# EPS_Connectors.net
KiCad netlist of a schematic drawn in Altium Designer
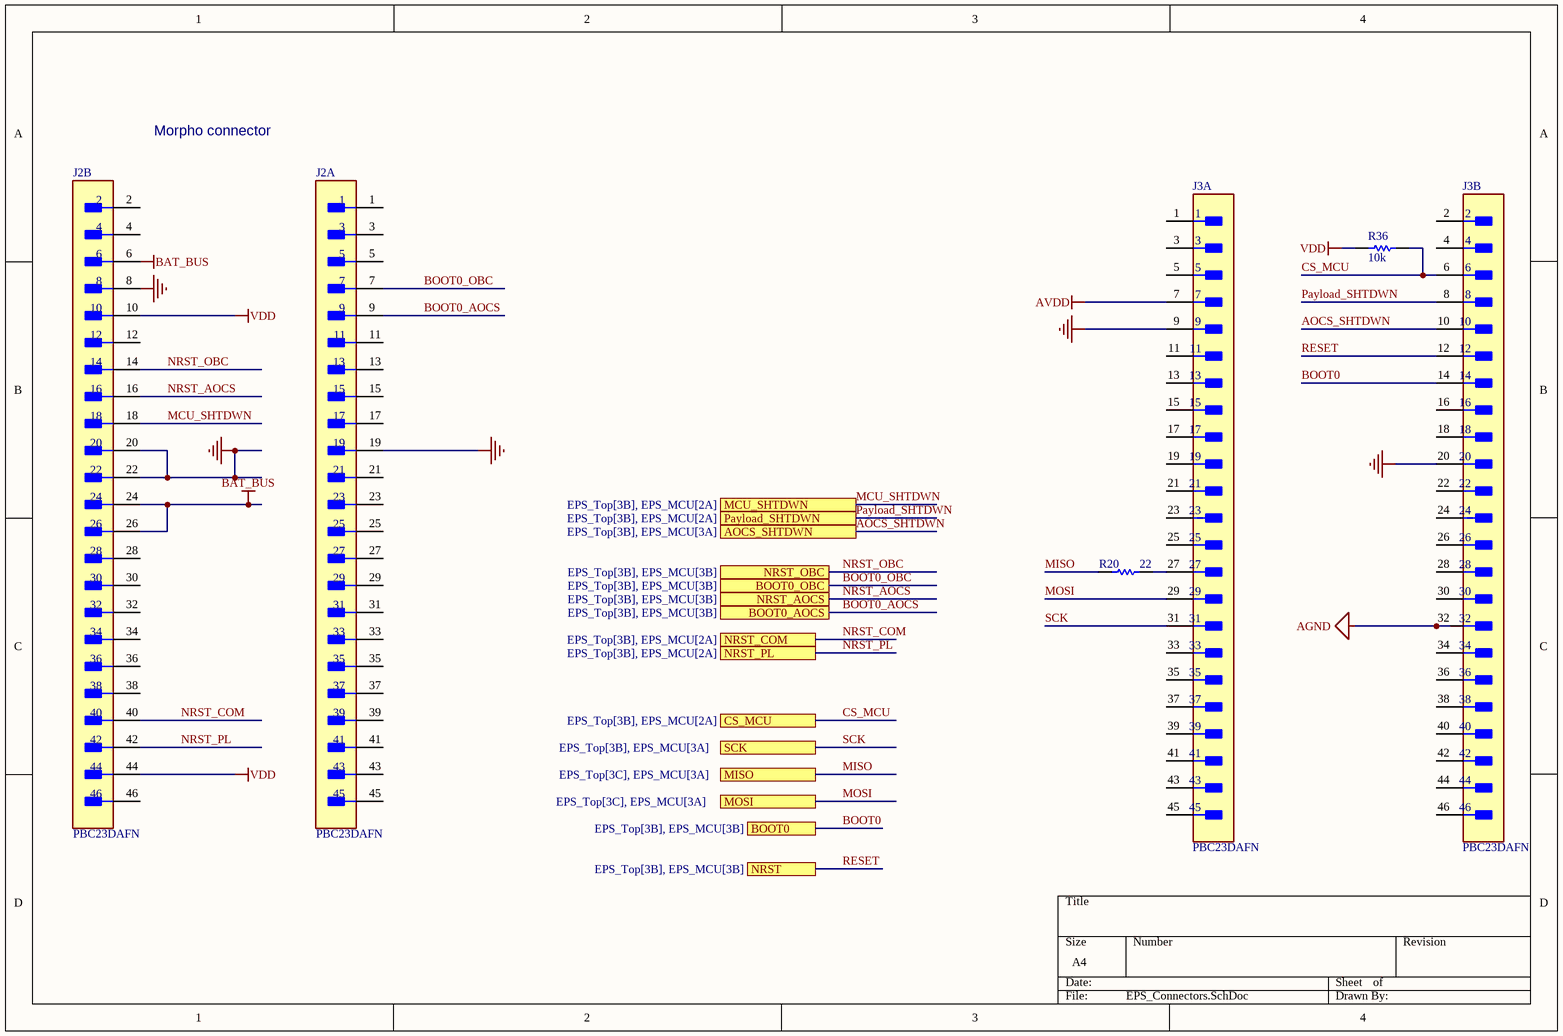
[diagram p0: EPS_Connectors.SchDoc]

(export (version "E")
  (design (tool "Eeschema 10.0.6"))
  (components
    (comp (ref "J2")
      (value "PBC23DAFN")
      (footprint "FP-PBC23DAFN-MFG")
      (description "CONN HEADER VERT 46POS 2.54MM")
      (libsource (lib "Altium Content Vault") (part "9d336348a4f8d78a7f3b81cc8d27765"))
    )
    (comp (ref "J3")
      (value "PBC23DAFN")
      (footprint "FP-PBC23DAFN-MFG")
      (description "CONN HEADER VERT 46POS 2.54MM")
      (libsource (lib "Altium Content Vault") (part "9d336348a4f8d78a7f3b81cc8d27765"))
    )
    (comp (ref "R20")
      (value "22")
      (footprint "RESC1608X55X25NL10T15")
      (description "Chip Resistor, 22 Ohm, +/- 1%, 0.1 W, -55 to 155 degC, 0603 (1608 Metric), RoHS, Tape and Reel")
      (libsource (lib "Altium Content Vault") (part "RES-2"))
    )
    (comp (ref "R36")
      (value "10k")
      (footprint "RESC1005X40X25LL05T05")
      (description "Chip Resistor, 10 KOhm, +/- 1%, 0.1 W, -55 to 155 degC, 0402 (1005 Metric), RoHS, Tape and Reel")
      (fields (field (name "TOLERANCE") "1%") (field (name "MANUFACTURER") "Panasonic"))
      (libsource (lib "Altium Content Vault") (part "RES-2"))
    )
  )
  (nets
    (net (code "1") (name "/AOCS_SHTDWN") (class "Default")
      (node (ref "J3") (pin "10") (pinfunction "10_10") (pintype "passive"))
    )
    (net (code "2") (name "/BOOT0") (class "Default")
      (node (ref "J3") (pin "14") (pinfunction "14_14") (pintype "passive"))
    )
    (net (code "3") (name "/BOOT0_AOCS") (class "Default")
      (node (ref "J2") (pin "9") (pinfunction "9_9") (pintype "passive"))
    )
    (net (code "4") (name "/BOOT0_OBC") (class "Default")
      (node (ref "J2") (pin "7") (pinfunction "7_7") (pintype "passive"))
    )
    (net (code "5") (name "/CS_MCU") (class "Default")
      (node (ref "J3") (pin "6") (pinfunction "6_6") (pintype "passive"))
      (node (ref "R36") (pin "1") (pinfunction "1_1") (pintype "passive"))
    )
    (net (code "6") (name "/MCU_SHTDWN") (class "Default")
      (node (ref "J2") (pin "18") (pinfunction "18_18") (pintype "passive"))
    )
    (net (code "7") (name "/MISO") (class "Default")
      (node (ref "R20") (pin "1") (pinfunction "1_1") (pintype "passive"))
    )
    (net (code "8") (name "/MOSI") (class "Default")
      (node (ref "J3") (pin "29") (pinfunction "29_29") (pintype "passive"))
    )
    (net (code "9") (name "/NRST_AOCS") (class "Default")
      (node (ref "J2") (pin "16") (pinfunction "16_16") (pintype "passive"))
    )
    (net (code "10") (name "/NRST_COM") (class "Default")
      (node (ref "J2") (pin "40") (pinfunction "40_40") (pintype "passive"))
    )
    (net (code "11") (name "/NRST_OBC") (class "Default")
      (node (ref "J2") (pin "14") (pinfunction "14_14") (pintype "passive"))
    )
    (net (code "12") (name "/NRST_PL") (class "Default")
      (node (ref "J2") (pin "42") (pinfunction "42_42") (pintype "passive"))
    )
    (net (code "13") (name "/Payload_SHTDWN") (class "Default")
      (node (ref "J3") (pin "8") (pinfunction "8_8") (pintype "passive"))
    )
    (net (code "14") (name "/RESET") (class "Default")
      (node (ref "J3") (pin "12") (pinfunction "12_12") (pintype "passive"))
    )
    (net (code "15") (name "/SCK") (class "Default")
      (node (ref "J3") (pin "31") (pinfunction "31_31") (pintype "passive"))
    )
    (net (code "16") (name "AGND") (class "Default")
      (node (ref "J3") (pin "32") (pinfunction "32_32") (pintype "passive"))
    )
    (net (code "17") (name "AVDD") (class "Default")
      (node (ref "J3") (pin "7") (pinfunction "7_7") (pintype "passive"))
    )
    (net (code "18") (name "BAT_BUS") (class "Default")
      (node (ref "J2") (pin "24") (pinfunction "24_24") (pintype "passive"))
      (node (ref "J2") (pin "26") (pinfunction "26_26") (pintype "passive"))
      (node (ref "J2") (pin "6") (pinfunction "6_6") (pintype "passive"))
    )
    (net (code "19") (name "GND") (class "Default")
      (node (ref "J2") (pin "19") (pinfunction "19_19") (pintype "passive"))
      (node (ref "J2") (pin "20") (pinfunction "20_20") (pintype "passive"))
      (node (ref "J2") (pin "22") (pinfunction "22_22") (pintype "passive"))
      (node (ref "J2") (pin "8") (pinfunction "8_8") (pintype "passive"))
      (node (ref "J3") (pin "20") (pinfunction "20_20") (pintype "passive"))
      (node (ref "J3") (pin "9") (pinfunction "9_9") (pintype "passive"))
    )
    (net (code "20") (name "Net-(J3-Pad27)") (class "Default")
      (node (ref "J3") (pin "27") (pinfunction "27_27") (pintype "passive"))
      (node (ref "R20") (pin "2") (pinfunction "2_2") (pintype "passive"))
    )
    (net (code "21") (name "VDD") (class "Default")
      (node (ref "J2") (pin "10") (pinfunction "10_10") (pintype "passive"))
      (node (ref "J2") (pin "44") (pinfunction "44_44") (pintype "passive"))
      (node (ref "R36") (pin "2") (pinfunction "2_2") (pintype "passive"))
    )
    (net (code "22") (name "unconnected-(J2-Pad1)") (class "Default")
      (node (ref "J2") (pin "1") (pinfunction "1_1") (pintype "passive"))
    )
    (net (code "23") (name "unconnected-(J2-Pad2)") (class "Default")
      (node (ref "J2") (pin "2") (pinfunction "2_2") (pintype "passive"))
    )
    (net (code "24") (name "unconnected-(J2-Pad3)") (class "Default")
      (node (ref "J2") (pin "3") (pinfunction "3_3") (pintype "passive"))
    )
    (net (code "25") (name "unconnected-(J2-Pad4)") (class "Default")
      (node (ref "J2") (pin "4") (pinfunction "4_4") (pintype "passive"))
    )
    (net (code "26") (name "unconnected-(J2-Pad5)") (class "Default")
      (node (ref "J2") (pin "5") (pinfunction "5_5") (pintype "passive"))
    )
    (net (code "27") (name "unconnected-(J2-Pad11)") (class "Default")
      (node (ref "J2") (pin "11") (pinfunction "11_11") (pintype "passive"))
    )
    (net (code "28") (name "unconnected-(J2-Pad12)") (class "Default")
      (node (ref "J2") (pin "12") (pinfunction "12_12") (pintype "passive"))
    )
    (net (code "29") (name "unconnected-(J2-Pad13)") (class "Default")
      (node (ref "J2") (pin "13") (pinfunction "13_13") (pintype "passive"))
    )
    (net (code "30") (name "unconnected-(J2-Pad15)") (class "Default")
      (node (ref "J2") (pin "15") (pinfunction "15_15") (pintype "passive"))
    )
    (net (code "31") (name "unconnected-(J2-Pad17)") (class "Default")
      (node (ref "J2") (pin "17") (pinfunction "17_17") (pintype "passive"))
    )
    (net (code "32") (name "unconnected-(J2-Pad21)") (class "Default")
      (node (ref "J2") (pin "21") (pinfunction "21_21") (pintype "passive"))
    )
    (net (code "33") (name "unconnected-(J2-Pad23)") (class "Default")
      (node (ref "J2") (pin "23") (pinfunction "23_23") (pintype "passive"))
    )
    (net (code "34") (name "unconnected-(J2-Pad25)") (class "Default")
      (node (ref "J2") (pin "25") (pinfunction "25_25") (pintype "passive"))
    )
    (net (code "35") (name "unconnected-(J2-Pad27)") (class "Default")
      (node (ref "J2") (pin "27") (pinfunction "27_27") (pintype "passive"))
    )
    (net (code "36") (name "unconnected-(J2-Pad28)") (class "Default")
      (node (ref "J2") (pin "28") (pinfunction "28_28") (pintype "passive"))
    )
    (net (code "37") (name "unconnected-(J2-Pad29)") (class "Default")
      (node (ref "J2") (pin "29") (pinfunction "29_29") (pintype "passive"))
    )
    (net (code "38") (name "unconnected-(J2-Pad30)") (class "Default")
      (node (ref "J2") (pin "30") (pinfunction "30_30") (pintype "passive"))
    )
    (net (code "39") (name "unconnected-(J2-Pad31)") (class "Default")
      (node (ref "J2") (pin "31") (pinfunction "31_31") (pintype "passive"))
    )
    (net (code "40") (name "unconnected-(J2-Pad32)") (class "Default")
      (node (ref "J2") (pin "32") (pinfunction "32_32") (pintype "passive"))
    )
    (net (code "41") (name "unconnected-(J2-Pad33)") (class "Default")
      (node (ref "J2") (pin "33") (pinfunction "33_33") (pintype "passive"))
    )
    (net (code "42") (name "unconnected-(J2-Pad34)") (class "Default")
      (node (ref "J2") (pin "34") (pinfunction "34_34") (pintype "passive"))
    )
    (net (code "43") (name "unconnected-(J2-Pad35)") (class "Default")
      (node (ref "J2") (pin "35") (pinfunction "35_35") (pintype "passive"))
    )
    (net (code "44") (name "unconnected-(J2-Pad36)") (class "Default")
      (node (ref "J2") (pin "36") (pinfunction "36_36") (pintype "passive"))
    )
    (net (code "45") (name "unconnected-(J2-Pad37)") (class "Default")
      (node (ref "J2") (pin "37") (pinfunction "37_37") (pintype "passive"))
    )
    (net (code "46") (name "unconnected-(J2-Pad38)") (class "Default")
      (node (ref "J2") (pin "38") (pinfunction "38_38") (pintype "passive"))
    )
    (net (code "47") (name "unconnected-(J2-Pad39)") (class "Default")
      (node (ref "J2") (pin "39") (pinfunction "39_39") (pintype "passive"))
    )
    (net (code "48") (name "unconnected-(J2-Pad41)") (class "Default")
      (node (ref "J2") (pin "41") (pinfunction "41_41") (pintype "passive"))
    )
    (net (code "49") (name "unconnected-(J2-Pad43)") (class "Default")
      (node (ref "J2") (pin "43") (pinfunction "43_43") (pintype "passive"))
    )
    (net (code "50") (name "unconnected-(J2-Pad45)") (class "Default")
      (node (ref "J2") (pin "45") (pinfunction "45_45") (pintype "passive"))
    )
    (net (code "51") (name "unconnected-(J2-Pad46)") (class "Default")
      (node (ref "J2") (pin "46") (pinfunction "46_46") (pintype "passive"))
    )
    (net (code "52") (name "unconnected-(J3-Pad1)") (class "Default")
      (node (ref "J3") (pin "1") (pinfunction "1_1") (pintype "passive"))
    )
    (net (code "53") (name "unconnected-(J3-Pad2)") (class "Default")
      (node (ref "J3") (pin "2") (pinfunction "2_2") (pintype "passive"))
    )
    (net (code "54") (name "unconnected-(J3-Pad3)") (class "Default")
      (node (ref "J3") (pin "3") (pinfunction "3_3") (pintype "passive"))
    )
    (net (code "55") (name "unconnected-(J3-Pad4)") (class "Default")
      (node (ref "J3") (pin "4") (pinfunction "4_4") (pintype "passive"))
    )
    (net (code "56") (name "unconnected-(J3-Pad5)") (class "Default")
      (node (ref "J3") (pin "5") (pinfunction "5_5") (pintype "passive"))
    )
    (net (code "57") (name "unconnected-(J3-Pad11)") (class "Default")
      (node (ref "J3") (pin "11") (pinfunction "11_11") (pintype "passive"))
    )
    (net (code "58") (name "unconnected-(J3-Pad13)") (class "Default")
      (node (ref "J3") (pin "13") (pinfunction "13_13") (pintype "passive"))
    )
    (net (code "59") (name "unconnected-(J3-Pad15)") (class "Default")
      (node (ref "J3") (pin "15") (pinfunction "15_15") (pintype "passive"))
    )
    (net (code "60") (name "unconnected-(J3-Pad16)") (class "Default")
      (node (ref "J3") (pin "16") (pinfunction "16_16") (pintype "passive"))
    )
    (net (code "61") (name "unconnected-(J3-Pad17)") (class "Default")
      (node (ref "J3") (pin "17") (pinfunction "17_17") (pintype "passive"))
    )
    (net (code "62") (name "unconnected-(J3-Pad18)") (class "Default")
      (node (ref "J3") (pin "18") (pinfunction "18_18") (pintype "passive"))
    )
    (net (code "63") (name "unconnected-(J3-Pad19)") (class "Default")
      (node (ref "J3") (pin "19") (pinfunction "19_19") (pintype "passive"))
    )
    (net (code "64") (name "unconnected-(J3-Pad21)") (class "Default")
      (node (ref "J3") (pin "21") (pinfunction "21_21") (pintype "passive"))
    )
    (net (code "65") (name "unconnected-(J3-Pad22)") (class "Default")
      (node (ref "J3") (pin "22") (pinfunction "22_22") (pintype "passive"))
    )
    (net (code "66") (name "unconnected-(J3-Pad23)") (class "Default")
      (node (ref "J3") (pin "23") (pinfunction "23_23") (pintype "passive"))
    )
    (net (code "67") (name "unconnected-(J3-Pad24)") (class "Default")
      (node (ref "J3") (pin "24") (pinfunction "24_24") (pintype "passive"))
    )
    (net (code "68") (name "unconnected-(J3-Pad25)") (class "Default")
      (node (ref "J3") (pin "25") (pinfunction "25_25") (pintype "passive"))
    )
    (net (code "69") (name "unconnected-(J3-Pad26)") (class "Default")
      (node (ref "J3") (pin "26") (pinfunction "26_26") (pintype "passive"))
    )
    (net (code "70") (name "unconnected-(J3-Pad28)") (class "Default")
      (node (ref "J3") (pin "28") (pinfunction "28_28") (pintype "passive"))
    )
    (net (code "71") (name "unconnected-(J3-Pad30)") (class "Default")
      (node (ref "J3") (pin "30") (pinfunction "30_30") (pintype "passive"))
    )
    (net (code "72") (name "unconnected-(J3-Pad33)") (class "Default")
      (node (ref "J3") (pin "33") (pinfunction "33_33") (pintype "passive"))
    )
    (net (code "73") (name "unconnected-(J3-Pad34)") (class "Default")
      (node (ref "J3") (pin "34") (pinfunction "34_34") (pintype "passive"))
    )
    (net (code "74") (name "unconnected-(J3-Pad35)") (class "Default")
      (node (ref "J3") (pin "35") (pinfunction "35_35") (pintype "passive"))
    )
    (net (code "75") (name "unconnected-(J3-Pad36)") (class "Default")
      (node (ref "J3") (pin "36") (pinfunction "36_36") (pintype "passive"))
    )
    (net (code "76") (name "unconnected-(J3-Pad37)") (class "Default")
      (node (ref "J3") (pin "37") (pinfunction "37_37") (pintype "passive"))
    )
    (net (code "77") (name "unconnected-(J3-Pad38)") (class "Default")
      (node (ref "J3") (pin "38") (pinfunction "38_38") (pintype "passive"))
    )
    (net (code "78") (name "unconnected-(J3-Pad39)") (class "Default")
      (node (ref "J3") (pin "39") (pinfunction "39_39") (pintype "passive"))
    )
    (net (code "79") (name "unconnected-(J3-Pad40)") (class "Default")
      (node (ref "J3") (pin "40") (pinfunction "40_40") (pintype "passive"))
    )
    (net (code "80") (name "unconnected-(J3-Pad41)") (class "Default")
      (node (ref "J3") (pin "41") (pinfunction "41_41") (pintype "passive"))
    )
    (net (code "81") (name "unconnected-(J3-Pad42)") (class "Default")
      (node (ref "J3") (pin "42") (pinfunction "42_42") (pintype "passive"))
    )
    (net (code "82") (name "unconnected-(J3-Pad43)") (class "Default")
      (node (ref "J3") (pin "43") (pinfunction "43_43") (pintype "passive"))
    )
    (net (code "83") (name "unconnected-(J3-Pad44)") (class "Default")
      (node (ref "J3") (pin "44") (pinfunction "44_44") (pintype "passive"))
    )
    (net (code "84") (name "unconnected-(J3-Pad45)") (class "Default")
      (node (ref "J3") (pin "45") (pinfunction "45_45") (pintype "passive"))
    )
    (net (code "85") (name "unconnected-(J3-Pad46)") (class "Default")
      (node (ref "J3") (pin "46") (pinfunction "46_46") (pintype "passive"))
    )
  )
)
